# Module.net
KiCad netlist of a schematic drawn in Altium Designer
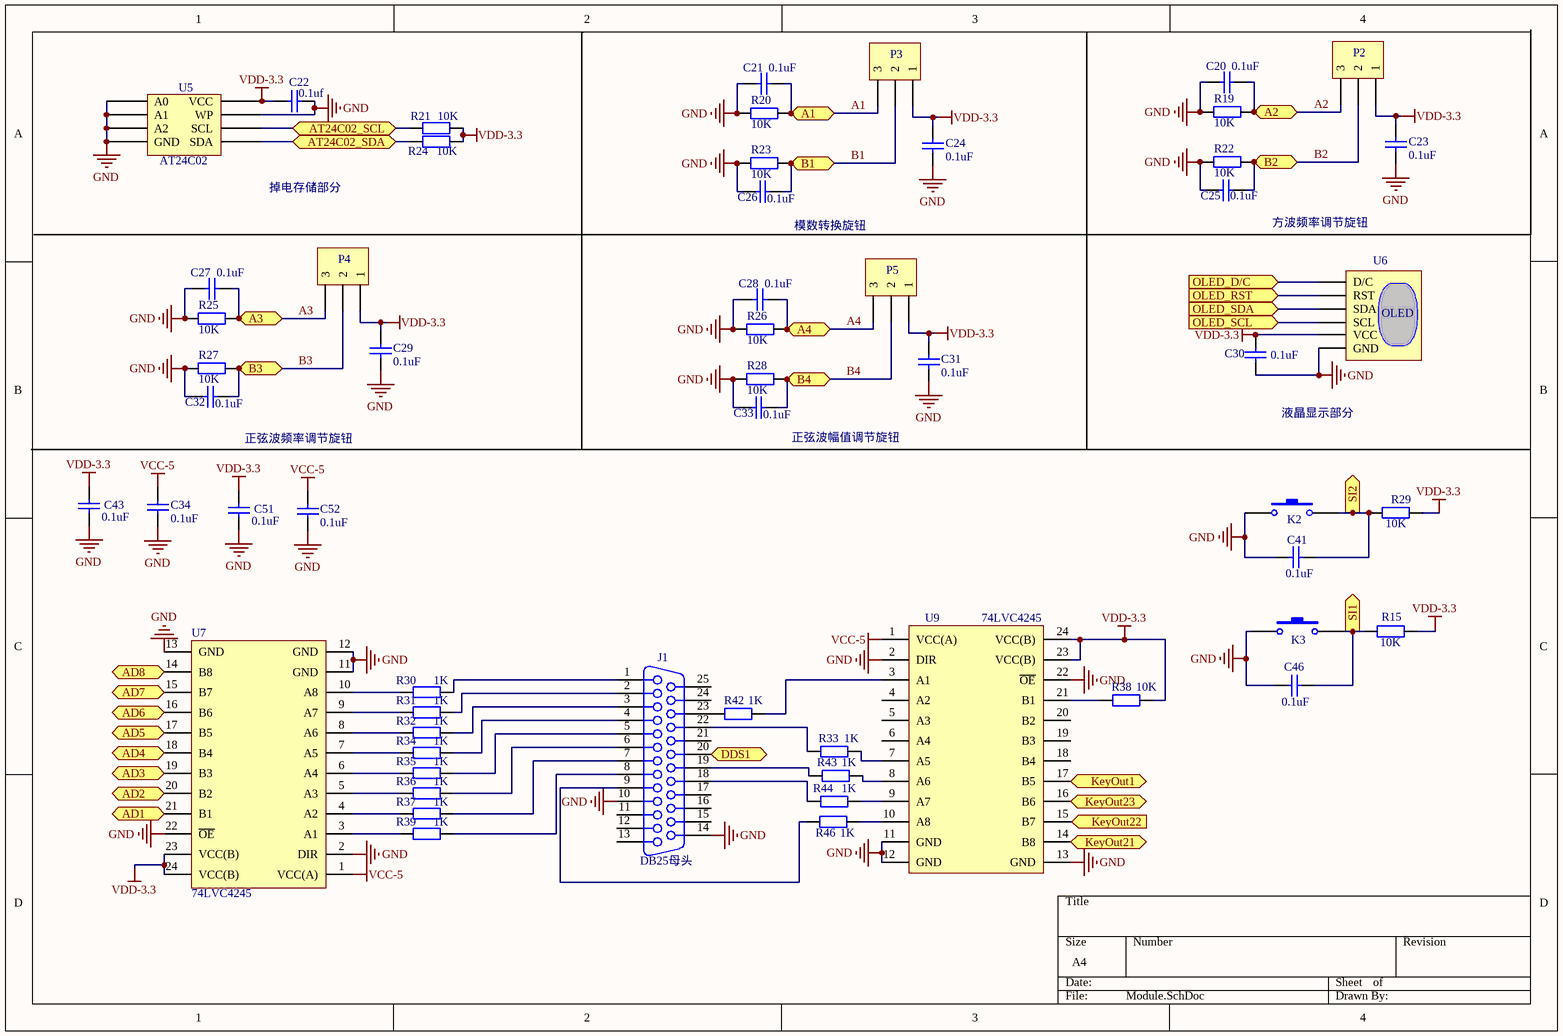
[diagram p0: Module.SchDoc]

(export (version "E")
  (design (tool "Eeschema 10.0.6"))
  (components
    (comp (ref "C20")
      (value "0.1uF")
      (footprint "0603")
      (fields (field (name "Comment") "Capacitor-0603"))
      (libsource (lib "原理图库") (part "Capacitor-0603"))
    )
    (comp (ref "C21")
      (value "0.1uF")
      (footprint "0603")
      (fields (field (name "Comment") "Capacitor-0603"))
      (libsource (lib "原理图库") (part "Capacitor-0603"))
    )
    (comp (ref "C22")
      (value "0.1uf")
      (footprint "0603")
      (fields (field (name "Comment") "Capacitor-0603"))
      (libsource (lib "原理图库") (part "Capacitor-0603"))
    )
    (comp (ref "C23")
      (value "0.1uF")
      (footprint "0603")
      (fields (field (name "Comment") "Capacitor-0603"))
      (libsource (lib "原理图库") (part "Capacitor-0603"))
    )
    (comp (ref "C24")
      (value "0.1uF")
      (footprint "0603")
      (fields (field (name "Comment") "Capacitor-0603"))
      (libsource (lib "原理图库") (part "Capacitor-0603"))
    )
    (comp (ref "C25")
      (value "0.1uF")
      (footprint "0603")
      (fields (field (name "Comment") "Capacitor-0603"))
      (libsource (lib "原理图库") (part "Capacitor-0603"))
    )
    (comp (ref "C26")
      (value "0.1uF")
      (footprint "0603")
      (fields (field (name "Comment") "Capacitor-0603"))
      (libsource (lib "原理图库") (part "Capacitor-0603"))
    )
    (comp (ref "C27")
      (value "0.1uF")
      (footprint "0603")
      (fields (field (name "Comment") "Capacitor-0603"))
      (libsource (lib "原理图库") (part "Capacitor-0603"))
    )
    (comp (ref "C28")
      (value "0.1uF")
      (footprint "0603")
      (fields (field (name "Comment") "Capacitor-0603"))
      (libsource (lib "原理图库") (part "Capacitor-0603"))
    )
    (comp (ref "C29")
      (value "0.1uF")
      (footprint "0603")
      (fields (field (name "Comment") "Capacitor-0603"))
      (libsource (lib "原理图库") (part "Capacitor-0603"))
    )
    (comp (ref "C30")
      (value "0.1uF")
      (footprint "0603")
      (fields (field (name "Comment") "Capacitor-0805"))
      (libsource (lib "原理图库") (part "Capacitor-0805"))
    )
    (comp (ref "C31")
      (value "0.1uF")
      (footprint "0603")
      (fields (field (name "Comment") "Capacitor-0603"))
      (libsource (lib "原理图库") (part "Capacitor-0603"))
    )
    (comp (ref "C32")
      (value "0.1uF")
      (footprint "0603")
      (fields (field (name "Comment") "Capacitor-0603"))
      (libsource (lib "原理图库") (part "Capacitor-0603"))
    )
    (comp (ref "C33")
      (value "0.1uF")
      (footprint "0603")
      (fields (field (name "Comment") "Capacitor-0603"))
      (libsource (lib "原理图库") (part "Capacitor-0603"))
    )
    (comp (ref "C34")
      (value "0.1uF")
      (footprint "0603")
      (fields (field (name "Comment") "Capacitor-0603"))
      (libsource (lib "原理图库") (part "Capacitor-0603"))
    )
    (comp (ref "C41")
      (value "0.1uF")
      (footprint "0603")
      (fields (field (name "Comment") "Capacitor-0603"))
      (libsource (lib "原理图库") (part "Capacitor-0603"))
    )
    (comp (ref "C43")
      (value "0.1uF")
      (footprint "0603")
      (fields (field (name "Comment") "Capacitor-0603"))
      (libsource (lib "原理图库") (part "Capacitor-0603"))
    )
    (comp (ref "C46")
      (value "0.1uF")
      (footprint "0603")
      (fields (field (name "Comment") "Capacitor-0603"))
      (libsource (lib "原理图库") (part "Capacitor-0603"))
    )
    (comp (ref "C51")
      (value "0.1uF")
      (footprint "0603")
      (fields (field (name "Comment") "Capacitor-0603"))
      (libsource (lib "原理图库") (part "Capacitor-0603"))
    )
    (comp (ref "C52")
      (value "0.1uF")
      (footprint "0603")
      (fields (field (name "Comment") "Capacitor-0603"))
      (libsource (lib "原理图库") (part "Capacitor-0603"))
    )
    (comp (ref "J1")
      (value "DB25母头")
      (footprint "DB25母头")
      (fields (field (name "Comment") "DB25"))
      (libsource (lib "原理图库") (part "DB25"))
    )
    (comp (ref "K2") (value "按键") (footprint "2MM接线端子") (libsource (lib "原理图库") (part "按键")))
    (comp (ref "K3") (value "按键") (footprint "2MM接线端子") (libsource (lib "原理图库") (part "按键")))
    (comp (ref "P2") (value "端子3") (footprint "3MM接线端子") (libsource (lib "原理图库") (part "端子3")))
    (comp (ref "P3") (value "端子3") (footprint "3MM接线端子") (libsource (lib "原理图库") (part "端子3")))
    (comp (ref "P4") (value "端子3") (footprint "3MM接线端子") (libsource (lib "原理图库") (part "端子3")))
    (comp (ref "P5") (value "端子3") (footprint "3MM接线端子") (libsource (lib "原理图库") (part "端子3")))
    (comp (ref "R15")
      (value "10K")
      (footprint "0603")
      (fields (field (name "Comment") "Resistor-0603"))
      (libsource (lib "") (part "Resistor-0603_1"))
    )
    (comp (ref "R19")
      (value "10K")
      (footprint "0603")
      (fields (field (name "Comment") "Resistor-0603"))
      (libsource (lib "原理图库") (part "Resistor-0603"))
    )
    (comp (ref "R20")
      (value "10K")
      (footprint "0603")
      (fields (field (name "Comment") "Resistor-0603"))
      (libsource (lib "原理图库") (part "Resistor-0603"))
    )
    (comp (ref "R21")
      (value "10K")
      (footprint "0603")
      (fields (field (name "Comment") "Resistor-0603"))
      (libsource (lib "") (part "Resistor-0603_1"))
    )
    (comp (ref "R22")
      (value "10K")
      (footprint "0603")
      (fields (field (name "Comment") "Resistor-0603"))
      (libsource (lib "原理图库") (part "Resistor-0603"))
    )
    (comp (ref "R23")
      (value "10K")
      (footprint "0603")
      (fields (field (name "Comment") "Resistor-0603"))
      (libsource (lib "原理图库") (part "Resistor-0603"))
    )
    (comp (ref "R24")
      (value "10K")
      (footprint "0603")
      (fields (field (name "Comment") "Resistor-0603"))
      (libsource (lib "") (part "Resistor-0603_1"))
    )
    (comp (ref "R25")
      (value "10K")
      (footprint "0603")
      (fields (field (name "Comment") "Resistor-0603"))
      (libsource (lib "原理图库") (part "Resistor-0603"))
    )
    (comp (ref "R26")
      (value "10K")
      (footprint "0603")
      (fields (field (name "Comment") "Resistor-0603"))
      (libsource (lib "原理图库") (part "Resistor-0603"))
    )
    (comp (ref "R27")
      (value "10K")
      (footprint "0603")
      (fields (field (name "Comment") "Resistor-0603"))
      (libsource (lib "原理图库") (part "Resistor-0603"))
    )
    (comp (ref "R28")
      (value "10K")
      (footprint "0603")
      (fields (field (name "Comment") "Resistor-0603"))
      (libsource (lib "原理图库") (part "Resistor-0603"))
    )
    (comp (ref "R29")
      (value "10K")
      (footprint "0603")
      (fields (field (name "Comment") "Resistor-0603"))
      (libsource (lib "原理图库") (part "Resistor-0603"))
    )
    (comp (ref "R30")
      (value "1K")
      (footprint "0603")
      (fields (field (name "Comment") "Resistor-0603"))
      (libsource (lib "原理图库") (part "Resistor-0603"))
    )
    (comp (ref "R31")
      (value "1K")
      (footprint "0603")
      (fields (field (name "Comment") "Resistor-0603"))
      (libsource (lib "原理图库") (part "Resistor-0603"))
    )
    (comp (ref "R32")
      (value "1K")
      (footprint "0603")
      (fields (field (name "Comment") "Resistor-0603"))
      (libsource (lib "原理图库") (part "Resistor-0603"))
    )
    (comp (ref "R33")
      (value "1K")
      (footprint "0603")
      (fields (field (name "Comment") "Resistor-0603"))
      (libsource (lib "原理图库") (part "Resistor-0603"))
    )
    (comp (ref "R34")
      (value "1K")
      (footprint "0603")
      (fields (field (name "Comment") "Resistor-0603"))
      (libsource (lib "原理图库") (part "Resistor-0603"))
    )
    (comp (ref "R35")
      (value "1K")
      (footprint "0603")
      (fields (field (name "Comment") "Resistor-0603"))
      (libsource (lib "原理图库") (part "Resistor-0603"))
    )
    (comp (ref "R36")
      (value "1K")
      (footprint "0603")
      (fields (field (name "Comment") "Resistor-0603"))
      (libsource (lib "原理图库") (part "Resistor-0603"))
    )
    (comp (ref "R37")
      (value "1K")
      (footprint "0603")
      (fields (field (name "Comment") "Resistor-0603"))
      (libsource (lib "原理图库") (part "Resistor-0603"))
    )
    (comp (ref "R38")
      (value "10K")
      (footprint "0603")
      (fields (field (name "Comment") "Resistor-0603"))
      (libsource (lib "原理图库") (part "Resistor-0603"))
    )
    (comp (ref "R39")
      (value "1K")
      (footprint "0603")
      (fields (field (name "Comment") "Resistor-0603"))
      (libsource (lib "原理图库") (part "Resistor-0603"))
    )
    (comp (ref "R42")
      (value "1K")
      (footprint "0603")
      (fields (field (name "Comment") "Resistor-0603"))
      (libsource (lib "原理图库") (part "Resistor-0603"))
    )
    (comp (ref "R43")
      (value "1K")
      (footprint "0603")
      (fields (field (name "Comment") "Resistor-0603"))
      (libsource (lib "原理图库") (part "Resistor-0603"))
    )
    (comp (ref "R44")
      (value "1K")
      (footprint "0603")
      (fields (field (name "Comment") "Resistor-0603"))
      (libsource (lib "原理图库") (part "Resistor-0603"))
    )
    (comp (ref "R46")
      (value "1K")
      (footprint "0603")
      (fields (field (name "Comment") "Resistor-0603"))
      (libsource (lib "原理图库") (part "Resistor-0603"))
    )
    (comp (ref "U5")
      (value "AT24C02")
      (footprint "AT24C02")
      (fields (field (name "NAME") "AT24C02"))
      (libsource (lib "原理图库") (part "AT24C02"))
    )
    (comp (ref "U6")
      (value "OLED")
      (footprint "OLED")
      (fields (field (name "NAME") "OLED"))
      (libsource (lib "原理图库") (part "OLED"))
    )
    (comp (ref "U7")
      (value "74LVC4245")
      (footprint "74LVC4245-PW")
      (fields (field (name "NAME") "74LVC4245"))
      (libsource (lib "原理图库") (part "74LVC4245"))
    )
    (comp (ref "U9")
      (value "74LVC4245")
      (footprint "74LVC4245-PW")
      (fields (field (name "NAME") "74LVC4245"))
      (libsource (lib "") (part "74LVC4245_1"))
    )
  )
  (nets
    (net (code "1") (name "/A1") (class "Default")
      (node (ref "C21") (pin "2") (pinfunction "2_2") (pintype "passive"))
      (node (ref "P3") (pin "3") (pinfunction "3_3") (pintype "passive"))
      (node (ref "R20") (pin "2") (pinfunction "2_2") (pintype "passive"))
    )
    (net (code "2") (name "/A2") (class "Default")
      (node (ref "C20") (pin "2") (pinfunction "2_2") (pintype "passive"))
      (node (ref "P2") (pin "3") (pinfunction "3_3") (pintype "passive"))
      (node (ref "R19") (pin "2") (pinfunction "2_2") (pintype "passive"))
    )
    (net (code "3") (name "/A3") (class "Default")
      (node (ref "C27") (pin "2") (pinfunction "2_2") (pintype "passive"))
      (node (ref "P4") (pin "3") (pinfunction "3_3") (pintype "passive"))
      (node (ref "R25") (pin "2") (pinfunction "2_2") (pintype "passive"))
    )
    (net (code "4") (name "/A4") (class "Default")
      (node (ref "C28") (pin "2") (pinfunction "2_2") (pintype "passive"))
      (node (ref "P5") (pin "3") (pinfunction "3_3") (pintype "passive"))
      (node (ref "R26") (pin "2") (pinfunction "2_2") (pintype "passive"))
    )
    (net (code "5") (name "/AD1") (class "Default")
      (node (ref "U7") (pin "21") (pinfunction "B1_21") (pintype "passive"))
    )
    (net (code "6") (name "/AD2") (class "Default")
      (node (ref "U7") (pin "20") (pinfunction "B2_20") (pintype "passive"))
    )
    (net (code "7") (name "/AD3") (class "Default")
      (node (ref "U7") (pin "19") (pinfunction "B3_19") (pintype "passive"))
    )
    (net (code "8") (name "/AD4") (class "Default")
      (node (ref "U7") (pin "18") (pinfunction "B4_18") (pintype "passive"))
    )
    (net (code "9") (name "/AD5") (class "Default")
      (node (ref "U7") (pin "17") (pinfunction "B5_17") (pintype "passive"))
    )
    (net (code "10") (name "/AD6") (class "Default")
      (node (ref "U7") (pin "16") (pinfunction "B6_16") (pintype "passive"))
    )
    (net (code "11") (name "/AD7") (class "Default")
      (node (ref "U7") (pin "15") (pinfunction "B7_15") (pintype "passive"))
    )
    (net (code "12") (name "/AD8") (class "Default")
      (node (ref "U7") (pin "14") (pinfunction "B8_14") (pintype "passive"))
    )
    (net (code "13") (name "/AT24C02_SCL") (class "Default")
      (node (ref "R21") (pin "2") (pinfunction "2_2") (pintype "passive"))
      (node (ref "U5") (pin "6") (pinfunction "SCL_6") (pintype "passive"))
    )
    (net (code "14") (name "/AT24C02_SDA") (class "Default")
      (node (ref "R24") (pin "2") (pinfunction "2_2") (pintype "passive"))
      (node (ref "U5") (pin "5") (pinfunction "SDA_5") (pintype "passive"))
    )
    (net (code "15") (name "/B1") (class "Default")
      (node (ref "C26") (pin "2") (pinfunction "2_2") (pintype "passive"))
      (node (ref "P3") (pin "2") (pinfunction "2_2") (pintype "passive"))
      (node (ref "R23") (pin "2") (pinfunction "2_2") (pintype "passive"))
    )
    (net (code "16") (name "/B2") (class "Default")
      (node (ref "C25") (pin "2") (pinfunction "2_2") (pintype "passive"))
      (node (ref "P2") (pin "2") (pinfunction "2_2") (pintype "passive"))
      (node (ref "R22") (pin "2") (pinfunction "2_2") (pintype "passive"))
    )
    (net (code "17") (name "/B3") (class "Default")
      (node (ref "C32") (pin "2") (pinfunction "2_2") (pintype "passive"))
      (node (ref "P4") (pin "2") (pinfunction "2_2") (pintype "passive"))
      (node (ref "R27") (pin "2") (pinfunction "2_2") (pintype "passive"))
    )
    (net (code "18") (name "/B4") (class "Default")
      (node (ref "C33") (pin "2") (pinfunction "2_2") (pintype "passive"))
      (node (ref "P5") (pin "2") (pinfunction "2_2") (pintype "passive"))
      (node (ref "R28") (pin "2") (pinfunction "2_2") (pintype "passive"))
    )
    (net (code "19") (name "/DDS1") (class "Default")
      (node (ref "J1") (pin "20") (pinfunction "20_20") (pintype "passive"))
    )
    (net (code "20") (name "/KeyOut1") (class "Default")
      (node (ref "U9") (pin "17") (pinfunction "B5_17") (pintype "passive"))
    )
    (net (code "21") (name "/KeyOut21") (class "Default")
      (node (ref "U9") (pin "14") (pinfunction "B8_14") (pintype "passive"))
    )
    (net (code "22") (name "/KeyOut22") (class "Default")
      (node (ref "U9") (pin "15") (pinfunction "B7_15") (pintype "passive"))
    )
    (net (code "23") (name "/KeyOut23") (class "Default")
      (node (ref "U9") (pin "16") (pinfunction "B6_16") (pintype "passive"))
    )
    (net (code "24") (name "/OLED_D{slash}C") (class "Default")
      (node (ref "U6") (pin "6") (pinfunction "D/C_6") (pintype "passive"))
    )
    (net (code "25") (name "/OLED_RST") (class "Default")
      (node (ref "U6") (pin "5") (pinfunction "RST_5") (pintype "passive"))
    )
    (net (code "26") (name "/OLED_SCL") (class "Default")
      (node (ref "U6") (pin "3") (pinfunction "SCL_3") (pintype "passive"))
    )
    (net (code "27") (name "/OLED_SDA") (class "Default")
      (node (ref "U6") (pin "4") (pinfunction "SDA_4") (pintype "passive"))
    )
    (net (code "28") (name "/SI1") (class "Default")
      (node (ref "C46") (pin "2") (pinfunction "2_2") (pintype "passive"))
      (node (ref "K3") (pin "2") (pinfunction "2_2") (pintype "passive"))
      (node (ref "R15") (pin "2") (pinfunction "2_2") (pintype "passive"))
    )
    (net (code "29") (name "/SI2") (class "Default")
      (node (ref "C41") (pin "2") (pinfunction "2_2") (pintype "passive"))
      (node (ref "K2") (pin "2") (pinfunction "2_2") (pintype "passive"))
      (node (ref "R29") (pin "1") (pinfunction "1_1") (pintype "passive"))
    )
    (net (code "30") (name "GND") (class "Default")
      (node (ref "C20") (pin "1") (pinfunction "1_1") (pintype "passive"))
      (node (ref "C21") (pin "1") (pinfunction "1_1") (pintype "passive"))
      (node (ref "C22") (pin "1") (pinfunction "1_1") (pintype "passive"))
      (node (ref "C23") (pin "2") (pinfunction "2_2") (pintype "passive"))
      (node (ref "C24") (pin "2") (pinfunction "2_2") (pintype "passive"))
      (node (ref "C25") (pin "1") (pinfunction "1_1") (pintype "passive"))
      (node (ref "C26") (pin "1") (pinfunction "1_1") (pintype "passive"))
      (node (ref "C27") (pin "1") (pinfunction "1_1") (pintype "passive"))
      (node (ref "C28") (pin "1") (pinfunction "1_1") (pintype "passive"))
      (node (ref "C29") (pin "2") (pinfunction "2_2") (pintype "passive"))
      (node (ref "C30") (pin "1") (pinfunction "1_1") (pintype "passive"))
      (node (ref "C31") (pin "2") (pinfunction "2_2") (pintype "passive"))
      (node (ref "C32") (pin "1") (pinfunction "1_1") (pintype "passive"))
      (node (ref "C33") (pin "1") (pinfunction "1_1") (pintype "passive"))
      (node (ref "C34") (pin "2") (pinfunction "2_2") (pintype "passive"))
      (node (ref "C41") (pin "1") (pinfunction "1_1") (pintype "passive"))
      (node (ref "C43") (pin "2") (pinfunction "2_2") (pintype "passive"))
      (node (ref "C46") (pin "1") (pinfunction "1_1") (pintype "passive"))
      (node (ref "C51") (pin "2") (pinfunction "2_2") (pintype "passive"))
      (node (ref "C52") (pin "2") (pinfunction "2_2") (pintype "passive"))
      (node (ref "J1") (pin "10") (pinfunction "10_10") (pintype "passive"))
      (node (ref "J1") (pin "14") (pinfunction "14_14") (pintype "passive"))
      (node (ref "K2") (pin "1") (pinfunction "1_1") (pintype "passive"))
      (node (ref "K3") (pin "1") (pinfunction "1_1") (pintype "passive"))
      (node (ref "R19") (pin "1") (pinfunction "1_1") (pintype "passive"))
      (node (ref "R20") (pin "1") (pinfunction "1_1") (pintype "passive"))
      (node (ref "R22") (pin "1") (pinfunction "1_1") (pintype "passive"))
      (node (ref "R23") (pin "1") (pinfunction "1_1") (pintype "passive"))
      (node (ref "R25") (pin "1") (pinfunction "1_1") (pintype "passive"))
      (node (ref "R26") (pin "1") (pinfunction "1_1") (pintype "passive"))
      (node (ref "R27") (pin "1") (pinfunction "1_1") (pintype "passive"))
      (node (ref "R28") (pin "1") (pinfunction "1_1") (pintype "passive"))
      (node (ref "U5") (pin "1") (pinfunction "A0_1") (pintype "passive"))
      (node (ref "U5") (pin "2") (pinfunction "A1_2") (pintype "passive"))
      (node (ref "U5") (pin "3") (pinfunction "A2_3") (pintype "passive"))
      (node (ref "U5") (pin "4") (pinfunction "GND_4") (pintype "passive"))
      (node (ref "U5") (pin "7") (pinfunction "WP_7") (pintype "passive"))
      (node (ref "U6") (pin "1") (pinfunction "GND_1") (pintype "passive"))
      (node (ref "U7") (pin "11") (pinfunction "GND_11") (pintype "passive"))
      (node (ref "U7") (pin "12") (pinfunction "GND_12") (pintype "passive"))
      (node (ref "U7") (pin "13") (pinfunction "GND_13") (pintype "passive"))
      (node (ref "U7") (pin "2") (pinfunction "DIR_2") (pintype "passive"))
      (node (ref "U7") (pin "22") (pinfunction "~{OE}_22") (pintype "passive"))
      (node (ref "U9") (pin "11") (pinfunction "GND_11") (pintype "passive"))
      (node (ref "U9") (pin "12") (pinfunction "GND_12") (pintype "passive"))
      (node (ref "U9") (pin "13") (pinfunction "GND_13") (pintype "passive"))
      (node (ref "U9") (pin "2") (pinfunction "DIR_2") (pintype "passive"))
      (node (ref "U9") (pin "22") (pinfunction "~{OE}_22") (pintype "passive"))
    )
    (net (code "31") (name "Net-(J1-Pad1)") (class "Default")
      (node (ref "J1") (pin "1") (pinfunction "1_1") (pintype "passive"))
      (node (ref "R30") (pin "2") (pinfunction "2_2") (pintype "passive"))
    )
    (net (code "32") (name "Net-(J1-Pad2)") (class "Default")
      (node (ref "J1") (pin "2") (pinfunction "2_2") (pintype "passive"))
      (node (ref "R31") (pin "2") (pinfunction "2_2") (pintype "passive"))
    )
    (net (code "33") (name "Net-(J1-Pad3)") (class "Default")
      (node (ref "J1") (pin "3") (pinfunction "3_3") (pintype "passive"))
      (node (ref "R32") (pin "2") (pinfunction "2_2") (pintype "passive"))
    )
    (net (code "34") (name "Net-(J1-Pad4)") (class "Default")
      (node (ref "J1") (pin "4") (pinfunction "4_4") (pintype "passive"))
      (node (ref "R34") (pin "2") (pinfunction "2_2") (pintype "passive"))
    )
    (net (code "35") (name "Net-(J1-Pad5)") (class "Default")
      (node (ref "J1") (pin "5") (pinfunction "5_5") (pintype "passive"))
      (node (ref "R35") (pin "2") (pinfunction "2_2") (pintype "passive"))
    )
    (net (code "36") (name "Net-(J1-Pad6)") (class "Default")
      (node (ref "J1") (pin "6") (pinfunction "6_6") (pintype "passive"))
      (node (ref "R36") (pin "2") (pinfunction "2_2") (pintype "passive"))
    )
    (net (code "37") (name "Net-(J1-Pad7)") (class "Default")
      (node (ref "J1") (pin "7") (pinfunction "7_7") (pintype "passive"))
      (node (ref "R37") (pin "2") (pinfunction "2_2") (pintype "passive"))
    )
    (net (code "38") (name "Net-(J1-Pad8)") (class "Default")
      (node (ref "J1") (pin "8") (pinfunction "8_8") (pintype "passive"))
      (node (ref "R39") (pin "2") (pinfunction "2_2") (pintype "passive"))
    )
    (net (code "39") (name "Net-(J1-Pad9)") (class "Default")
      (node (ref "J1") (pin "9") (pinfunction "9_9") (pintype "passive"))
      (node (ref "R46") (pin "1") (pinfunction "1_1") (pintype "passive"))
    )
    (net (code "40") (name "Net-(J1-Pad18)") (class "Default")
      (node (ref "J1") (pin "18") (pinfunction "18_18") (pintype "passive"))
      (node (ref "R44") (pin "1") (pinfunction "1_1") (pintype "passive"))
    )
    (net (code "41") (name "Net-(J1-Pad19)") (class "Default")
      (node (ref "J1") (pin "19") (pinfunction "19_19") (pintype "passive"))
      (node (ref "R43") (pin "1") (pinfunction "1_1") (pintype "passive"))
    )
    (net (code "42") (name "Net-(J1-Pad22)") (class "Default")
      (node (ref "J1") (pin "22") (pinfunction "22_22") (pintype "passive"))
      (node (ref "R33") (pin "1") (pinfunction "1_1") (pintype "passive"))
    )
    (net (code "43") (name "Net-(J1-Pad23)") (class "Default")
      (node (ref "J1") (pin "23") (pinfunction "23_23") (pintype "passive"))
      (node (ref "R42") (pin "1") (pinfunction "1_1") (pintype "passive"))
    )
    (net (code "44") (name "Net-(U7-A1)") (class "Default")
      (node (ref "R39") (pin "1") (pinfunction "1_1") (pintype "passive"))
      (node (ref "U7") (pin "3") (pinfunction "A1_3") (pintype "passive"))
    )
    (net (code "45") (name "Net-(U7-A2)") (class "Default")
      (node (ref "R37") (pin "1") (pinfunction "1_1") (pintype "passive"))
      (node (ref "U7") (pin "4") (pinfunction "A2_4") (pintype "passive"))
    )
    (net (code "46") (name "Net-(U7-A3)") (class "Default")
      (node (ref "R36") (pin "1") (pinfunction "1_1") (pintype "passive"))
      (node (ref "U7") (pin "5") (pinfunction "A3_5") (pintype "passive"))
    )
    (net (code "47") (name "Net-(U7-A4)") (class "Default")
      (node (ref "R35") (pin "1") (pinfunction "1_1") (pintype "passive"))
      (node (ref "U7") (pin "6") (pinfunction "A4_6") (pintype "passive"))
    )
    (net (code "48") (name "Net-(U7-A5)") (class "Default")
      (node (ref "R34") (pin "1") (pinfunction "1_1") (pintype "passive"))
      (node (ref "U7") (pin "7") (pinfunction "A5_7") (pintype "passive"))
    )
    (net (code "49") (name "Net-(U7-A6)") (class "Default")
      (node (ref "R32") (pin "1") (pinfunction "1_1") (pintype "passive"))
      (node (ref "U7") (pin "8") (pinfunction "A6_8") (pintype "passive"))
    )
    (net (code "50") (name "Net-(U7-A7)") (class "Default")
      (node (ref "R31") (pin "1") (pinfunction "1_1") (pintype "passive"))
      (node (ref "U7") (pin "9") (pinfunction "A7_9") (pintype "passive"))
    )
    (net (code "51") (name "Net-(U7-A8)") (class "Default")
      (node (ref "R30") (pin "1") (pinfunction "1_1") (pintype "passive"))
      (node (ref "U7") (pin "10") (pinfunction "A8_10") (pintype "passive"))
    )
    (net (code "52") (name "Net-(U9-A1)") (class "Default")
      (node (ref "R42") (pin "2") (pinfunction "2_2") (pintype "passive"))
      (node (ref "U9") (pin "3") (pinfunction "A1_3") (pintype "passive"))
    )
    (net (code "53") (name "Net-(U9-A5)") (class "Default")
      (node (ref "R33") (pin "2") (pinfunction "2_2") (pintype "passive"))
      (node (ref "U9") (pin "7") (pinfunction "A5_7") (pintype "passive"))
    )
    (net (code "54") (name "Net-(U9-A6)") (class "Default")
      (node (ref "R43") (pin "2") (pinfunction "2_2") (pintype "passive"))
      (node (ref "U9") (pin "8") (pinfunction "A6_8") (pintype "passive"))
    )
    (net (code "55") (name "Net-(U9-A7)") (class "Default")
      (node (ref "R44") (pin "2") (pinfunction "2_2") (pintype "passive"))
      (node (ref "U9") (pin "9") (pinfunction "A7_9") (pintype "passive"))
    )
    (net (code "56") (name "Net-(U9-A8)") (class "Default")
      (node (ref "R46") (pin "2") (pinfunction "2_2") (pintype "passive"))
      (node (ref "U9") (pin "10") (pinfunction "A8_10") (pintype "passive"))
    )
    (net (code "57") (name "Net-(U9-B1)") (class "Default")
      (node (ref "R38") (pin "1") (pinfunction "1_1") (pintype "passive"))
      (node (ref "U9") (pin "21") (pinfunction "B1_21") (pintype "passive"))
    )
    (net (code "58") (name "VCC-5") (class "Default")
      (node (ref "C34") (pin "1") (pinfunction "1_1") (pintype "passive"))
      (node (ref "C52") (pin "1") (pinfunction "1_1") (pintype "passive"))
      (node (ref "U7") (pin "1") (pinfunction "VCC(A)_1") (pintype "passive"))
      (node (ref "U9") (pin "1") (pinfunction "VCC(A)_1") (pintype "passive"))
    )
    (net (code "59") (name "VDD-3.3") (class "Default")
      (node (ref "C22") (pin "2") (pinfunction "2_2") (pintype "passive"))
      (node (ref "C23") (pin "1") (pinfunction "1_1") (pintype "passive"))
      (node (ref "C24") (pin "1") (pinfunction "1_1") (pintype "passive"))
      (node (ref "C29") (pin "1") (pinfunction "1_1") (pintype "passive"))
      (node (ref "C30") (pin "2") (pinfunction "2_2") (pintype "passive"))
      (node (ref "C31") (pin "1") (pinfunction "1_1") (pintype "passive"))
      (node (ref "C43") (pin "1") (pinfunction "1_1") (pintype "passive"))
      (node (ref "C51") (pin "1") (pinfunction "1_1") (pintype "passive"))
      (node (ref "P2") (pin "1") (pinfunction "1_1") (pintype "passive"))
      (node (ref "P3") (pin "1") (pinfunction "1_1") (pintype "passive"))
      (node (ref "P4") (pin "1") (pinfunction "1_1") (pintype "passive"))
      (node (ref "P5") (pin "1") (pinfunction "1_1") (pintype "passive"))
      (node (ref "R15") (pin "1") (pinfunction "1_1") (pintype "passive"))
      (node (ref "R21") (pin "1") (pinfunction "1_1") (pintype "passive"))
      (node (ref "R24") (pin "1") (pinfunction "1_1") (pintype "passive"))
      (node (ref "R29") (pin "2") (pinfunction "2_2") (pintype "passive"))
      (node (ref "R38") (pin "2") (pinfunction "2_2") (pintype "passive"))
      (node (ref "U5") (pin "8") (pinfunction "VCC_8") (pintype "passive"))
      (node (ref "U6") (pin "2") (pinfunction "VCC_2") (pintype "passive"))
      (node (ref "U7") (pin "23") (pinfunction "VCC(B)_23") (pintype "passive"))
      (node (ref "U7") (pin "24") (pinfunction "VCC(B)_24") (pintype "passive"))
      (node (ref "U9") (pin "23") (pinfunction "VCC(B)_23") (pintype "passive"))
      (node (ref "U9") (pin "24") (pinfunction "VCC(B)_24") (pintype "passive"))
    )
    (net (code "60") (name "unconnected-(J1-Pad11)") (class "Default")
      (node (ref "J1") (pin "11") (pinfunction "11_11") (pintype "passive"))
    )
    (net (code "61") (name "unconnected-(J1-Pad12)") (class "Default")
      (node (ref "J1") (pin "12") (pinfunction "12_12") (pintype "passive"))
    )
    (net (code "62") (name "unconnected-(J1-Pad13)") (class "Default")
      (node (ref "J1") (pin "13") (pinfunction "13_13") (pintype "passive"))
    )
    (net (code "63") (name "unconnected-(J1-Pad15)") (class "Default")
      (node (ref "J1") (pin "15") (pinfunction "15_15") (pintype "passive"))
    )
    (net (code "64") (name "unconnected-(J1-Pad16)") (class "Default")
      (node (ref "J1") (pin "16") (pinfunction "16_16") (pintype "passive"))
    )
    (net (code "65") (name "unconnected-(J1-Pad17)") (class "Default")
      (node (ref "J1") (pin "17") (pinfunction "17_17") (pintype "passive"))
    )
    (net (code "66") (name "unconnected-(J1-Pad21)") (class "Default")
      (node (ref "J1") (pin "21") (pinfunction "21_21") (pintype "passive"))
    )
    (net (code "67") (name "unconnected-(J1-Pad24)") (class "Default")
      (node (ref "J1") (pin "24") (pinfunction "24_24") (pintype "passive"))
    )
    (net (code "68") (name "unconnected-(J1-Pad25)") (class "Default")
      (node (ref "J1") (pin "25") (pinfunction "25_25") (pintype "passive"))
    )
    (net (code "69") (name "unconnected-(U9-A2-Pad4)") (class "Default")
      (node (ref "U9") (pin "4") (pinfunction "A2_4") (pintype "passive"))
    )
    (net (code "70") (name "unconnected-(U9-A3-Pad5)") (class "Default")
      (node (ref "U9") (pin "5") (pinfunction "A3_5") (pintype "passive"))
    )
    (net (code "71") (name "unconnected-(U9-A4-Pad6)") (class "Default")
      (node (ref "U9") (pin "6") (pinfunction "A4_6") (pintype "passive"))
    )
    (net (code "72") (name "unconnected-(U9-B2-Pad20)") (class "Default")
      (node (ref "U9") (pin "20") (pinfunction "B2_20") (pintype "passive"))
    )
    (net (code "73") (name "unconnected-(U9-B3-Pad19)") (class "Default")
      (node (ref "U9") (pin "19") (pinfunction "B3_19") (pintype "passive"))
    )
    (net (code "74") (name "unconnected-(U9-B4-Pad18)") (class "Default")
      (node (ref "U9") (pin "18") (pinfunction "B4_18") (pintype "passive"))
    )
  )
)
